# UART_TO_RS232.net
KiCad netlist of a schematic drawn in Altium Designer
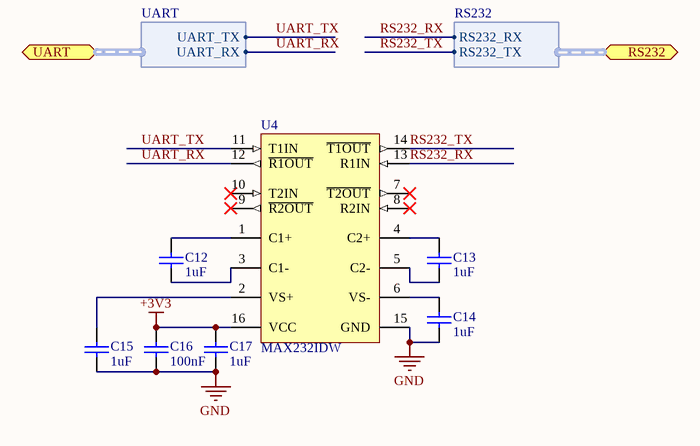
[diagram p0: UART_TO_RS232.SchDoc]

(export (version "E")
  (design (tool "Eeschema 10.0.6"))
  (components
    (comp (ref "C12")
      (value "1uF")
      (footprint "CAP_0805_IPC_MD")
      (description "Capacitor")
      (fields (field (name "MANUFACTURER") "Samsung") (field (name "Comment") "Cap"))
      (libsource (lib "DataLogger") (part "Cap"))
    )
    (comp (ref "C13")
      (value "1uF")
      (footprint "CAP_0805_IPC_MD")
      (description "Capacitor")
      (fields (field (name "MANUFACTURER") "Samsung") (field (name "Comment") "Cap"))
      (libsource (lib "DataLogger") (part "Cap"))
    )
    (comp (ref "C14")
      (value "1uF")
      (footprint "CAP_0805_IPC_MD")
      (description "Capacitor")
      (fields (field (name "MANUFACTURER") "Samsung") (field (name "Comment") "Cap"))
      (libsource (lib "DataLogger") (part "Cap"))
    )
    (comp (ref "C15")
      (value "1uF")
      (footprint "CAP_0805_IPC_MD")
      (description "Capacitor")
      (fields (field (name "MANUFACTURER") "Samsung") (field (name "Comment") "Cap"))
      (libsource (lib "DataLogger") (part "Cap"))
    )
    (comp (ref "C16")
      (value "100nF")
      (footprint "CAP_0805_IPC_MD")
      (description "Capacitor")
      (fields (field (name "MANUFACTURER") "Samsung") (field (name "Comment") "Cap"))
      (libsource (lib "DataLogger") (part "Cap"))
    )
    (comp (ref "C17")
      (value "1uF")
      (footprint "CAP_0805_IPC_MD")
      (description "Capacitor")
      (fields (field (name "MANUFACTURER") "Samsung") (field (name "Comment") "Cap"))
      (libsource (lib "DataLogger") (part "Cap"))
    )
    (comp (ref "U4")
      (value "MAX232IDW")
      (footprint "SO_16_IPC_MD")
      (description "Dual EIA-232 Driver / Receiver, -40 to 85 degC, 16-Pin SOIC (DW), Green (RoHS & no Sb/Br)")
      (fields (field (name "MANUFACTURER") "Texas Instruments"))
      (libsource (lib "DataLogger") (part "MAX232IDW"))
    )
  )
  (nets
    (net (code "3") (name "+3V3") (class "Default")
      (node (ref "C16") (pin "2") (pinfunction "2_2") (pintype "passive"))
      (node (ref "C17") (pin "2") (pinfunction "2_2") (pintype "passive"))
      (node (ref "U4") (pin "16") (pinfunction "VCC_16") (pintype "power_in"))
    )
    (net (code "4") (name "/RS232_RX") (class "Default")
      (node (ref "U4") (pin "13") (pinfunction "R1IN_13") (pintype "input"))
    )
    (net (code "5") (name "/RS232_TX") (class "Default")
      (node (ref "U4") (pin "14") (pinfunction "~{T1OUT}_14") (pintype "output"))
    )
    (net (code "6") (name "/UART_RX") (class "Default")
      (node (ref "U4") (pin "12") (pinfunction "~{R1OUT}_12") (pintype "output"))
    )
    (net (code "7") (name "/UART_TX") (class "Default")
      (node (ref "U4") (pin "11") (pinfunction "T1IN_11") (pintype "input"))
    )
    (net (code "10") (name "GND") (class "Default")
      (node (ref "C14") (pin "1") (pinfunction "1_1") (pintype "passive"))
      (node (ref "C15") (pin "1") (pinfunction "1_1") (pintype "passive"))
      (node (ref "C16") (pin "1") (pinfunction "1_1") (pintype "passive"))
      (node (ref "C17") (pin "1") (pinfunction "1_1") (pintype "passive"))
      (node (ref "U4") (pin "15") (pinfunction "GND_15") (pintype "power_in"))
    )
    (net (code "11") (name "Net-(U4-C1+)") (class "Default")
      (node (ref "C12") (pin "2") (pinfunction "2_2") (pintype "passive"))
      (node (ref "U4") (pin "1") (pinfunction "C1+_1") (pintype "passive"))
    )
    (net (code "12") (name "Net-(U4-C1-)") (class "Default")
      (node (ref "C12") (pin "1") (pinfunction "1_1") (pintype "passive"))
      (node (ref "U4") (pin "3") (pinfunction "C1-_3") (pintype "passive"))
    )
    (net (code "13") (name "Net-(U4-C2+)") (class "Default")
      (node (ref "C13") (pin "2") (pinfunction "2_2") (pintype "passive"))
      (node (ref "U4") (pin "4") (pinfunction "C2+_4") (pintype "passive"))
    )
    (net (code "14") (name "Net-(U4-C2-)") (class "Default")
      (node (ref "C13") (pin "1") (pinfunction "1_1") (pintype "passive"))
      (node (ref "U4") (pin "5") (pinfunction "C2-_5") (pintype "passive"))
    )
    (net (code "15") (name "Net-(U4-VS+)") (class "Default")
      (node (ref "C15") (pin "2") (pinfunction "2_2") (pintype "passive"))
      (node (ref "U4") (pin "2") (pinfunction "VS+_2") (pintype "power_in"))
    )
    (net (code "16") (name "Net-(U4-VS-)") (class "Default")
      (node (ref "C14") (pin "2") (pinfunction "2_2") (pintype "passive"))
      (node (ref "U4") (pin "6") (pinfunction "VS-_6") (pintype "power_in"))
    )
    (net (code "17") (name "unconnected-(U4-R2IN-Pad8)") (class "Default")
      (node (ref "U4") (pin "8") (pinfunction "R2IN_8") (pintype "input+no_connect"))
    )
    (net (code "18") (name "unconnected-(U4-T2IN-Pad10)") (class "Default")
      (node (ref "U4") (pin "10") (pinfunction "T2IN_10") (pintype "input+no_connect"))
    )
    (net (code "19") (name "unconnected-(U4-~{R2OUT}-Pad9)") (class "Default")
      (node (ref "U4") (pin "9") (pinfunction "~{R2OUT}_9") (pintype "output+no_connect"))
    )
    (net (code "20") (name "unconnected-(U4-~{T2OUT}-Pad7)") (class "Default")
      (node (ref "U4") (pin "7") (pinfunction "~{T2OUT}_7") (pintype "output+no_connect"))
    )
  )
)
